# VCO_BFP420.net
KiCad netlist of a schematic drawn in Altium Designer
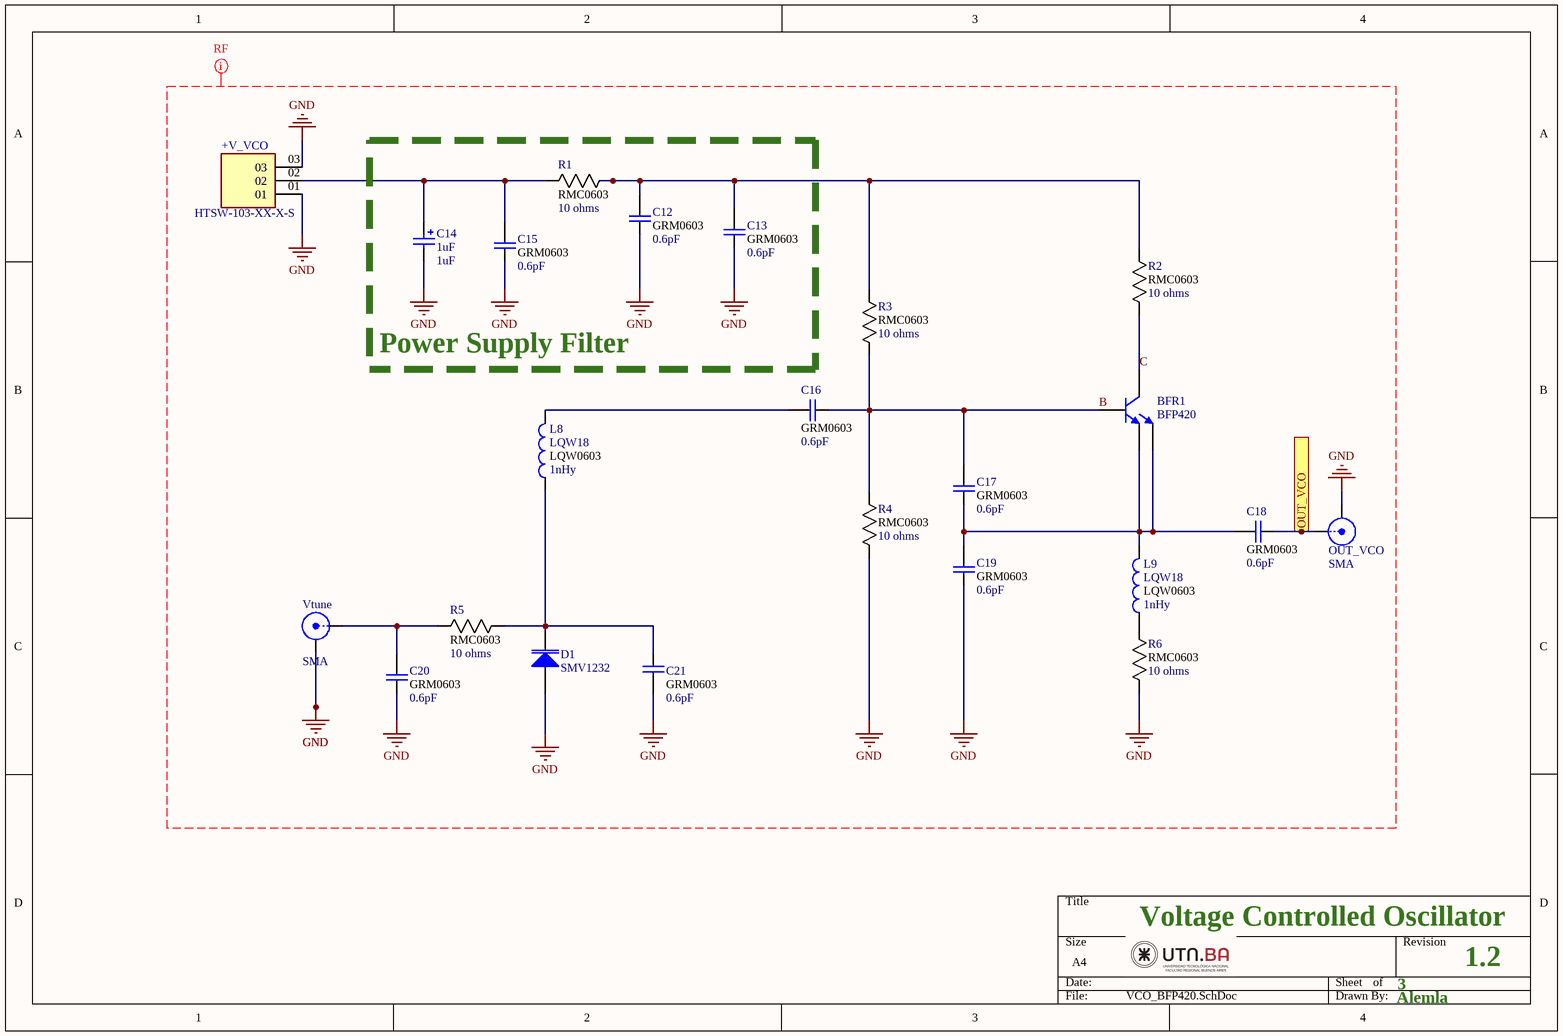
[diagram p0: VCO_BFP420.SchDoc]

(export (version "E")
  (design (tool "Eeschema 10.0.6"))
  (components
    (comp (ref "+V_VCO")
      (value "HTSW-103-XX-X-S")
      (footprint "SAMTEC_HTSW-103-XX-X-S")
      (description "Conn Unshrouded Header HDR 3 POS 2.54mm Solder ST Top Entry Thru-Hole Bag")
      (fields (field (name "MP") "HTSW-103-08-S-S") (field (name "MF") "Samtec"))
      (libsource (lib "HTSW-103-XX-X-S") (part "HTSW-103-XX-X-S"))
    )
    (comp (ref "BFR1")
      (value "BFP420")
      (footprint "SOT-343_N")
      (description "NPN Bipolar Transistor")
      (fields (field (name "PUBLISHER") "Altium Limited"))
      (libsource (lib "PCB_Project") (part "BFR460"))
    )
    (comp (ref "C12")
      (value "0.6pF")
      (footprint "GRM0603")
      (description "Capacitor GRM18 0603")
      (fields (field (name "Comment") "Cap 0603") (field (name "PUBLISHER") "Altium Limited"))
      (libsource (lib "Radar_RF_EAIII") (part "Cap"))
    )
    (comp (ref "C13")
      (value "0.6pF")
      (footprint "GRM0603")
      (description "Capacitor GRM18 0603")
      (fields (field (name "Comment") "Cap 0603") (field (name "PUBLISHER") "Altium Limited"))
      (libsource (lib "Radar_RF_EAIII") (part "Cap"))
    )
    (comp (ref "C14")
      (value "1uF")
      (footprint "6-0805_N")
      (description "Polarized Capacitor (Axial)")
      (fields (field (name "ALTIUM_VALUE") "1uF") (field (name "PUBLISHER") "Altium Limited"))
      (libsource (lib "PCB_Project") (part "Cap Pol2_1"))
    )
    (comp (ref "C15")
      (value "0.6pF")
      (footprint "GRM0603")
      (description "Capacitor GRM18 0603")
      (fields (field (name "Comment") "Cap 0603") (field (name "PUBLISHER") "Altium Limited"))
      (libsource (lib "Radar_RF_EAIII") (part "Cap"))
    )
    (comp (ref "C16")
      (value "0.6pF")
      (footprint "GRM0603")
      (description "Capacitor GRM18 0603")
      (fields (field (name "Comment") "Cap 0603") (field (name "PUBLISHER") "Altium Limited"))
      (libsource (lib "Radar_RF_EAIII") (part "Cap"))
    )
    (comp (ref "C17")
      (value "0.6pF")
      (footprint "GRM0603")
      (description "Capacitor GRM18 0603")
      (fields (field (name "Comment") "Cap 0603") (field (name "PUBLISHER") "Altium Limited"))
      (libsource (lib "Radar_RF_EAIII") (part "Cap"))
    )
    (comp (ref "C18")
      (value "0.6pF")
      (footprint "GRM0603")
      (description "Capacitor GRM18 0603")
      (fields (field (name "Comment") "Cap 0603") (field (name "PUBLISHER") "Altium Limited"))
      (libsource (lib "Radar_RF_EAIII") (part "Cap"))
    )
    (comp (ref "C19")
      (value "0.6pF")
      (footprint "GRM0603")
      (description "Capacitor GRM18 0603")
      (fields (field (name "Comment") "Cap 0603") (field (name "PUBLISHER") "Altium Limited"))
      (libsource (lib "Radar_RF_EAIII") (part "Cap"))
    )
    (comp (ref "C20")
      (value "0.6pF")
      (footprint "GRM0603")
      (description "Capacitor GRM18 0603")
      (fields (field (name "Comment") "Cap 0603") (field (name "PUBLISHER") "Altium Limited"))
      (libsource (lib "Radar_RF_EAIII") (part "Cap"))
    )
    (comp (ref "C21")
      (value "0.6pF")
      (footprint "GRM0603")
      (description "Capacitor GRM18 0603")
      (fields (field (name "Comment") "Cap 0603") (field (name "PUBLISHER") "Altium Limited"))
      (libsource (lib "Radar_RF_EAIII") (part "Cap"))
    )
    (comp (ref "D1")
      (value "SMV1232")
      (footprint "6-0805_N")
      (description "Variable Capacitance Diode")
      (fields (field (name "PUBLISHER") "Altium Limited"))
      (libsource (lib "Radar_RF_EAIII") (part "D Varactor"))
    )
    (comp (ref "L8")
      (value "LQW18")
      (footprint "INDC1608X100N")
      (description "Ind RF Chip Wirewound 18nH 5% 100MHz 40Q-Factor 550mA 0603 Paper T/R")
      (fields
        (field (name "MP") "LQW18AN18NJ00D")
        (field (name "PARAMETER 1") "LQW0603")
        (field (name "ALTIUM_VALUE") "1nHy")
      )
      (libsource (lib "Radar_RF_EAIII") (part "LQW18"))
    )
    (comp (ref "L9")
      (value "LQW18")
      (footprint "INDC1608X100N")
      (description "Ind RF Chip Wirewound 18nH 5% 100MHz 40Q-Factor 550mA 0603 Paper T/R")
      (fields
        (field (name "MP") "LQW18AN18NJ00D")
        (field (name "PARAMETER 1") "LQW0603")
        (field (name "ALTIUM_VALUE") "1nHy")
      )
      (libsource (lib "Radar_RF_EAIII") (part "LQW18"))
    )
    (comp (ref "OUT_VCO")
      (value "SMA")
      (footprint "SMA-142-0701-851")
      (description "SMA Straight Connector")
      (fields (field (name "PUBLISHER") "Altium Limited"))
      (libsource (lib "Radar_RF_EAIII") (part "SMA"))
    )
    (comp (ref "R1")
      (value "10 ohms")
      (footprint "RMC0603")
      (description "Resistor RMC0603")
      (fields (field (name "Comment") "Resistor"))
      (libsource (lib "Radar_RF_EAIII") (part "Resistor"))
    )
    (comp (ref "R2")
      (value "10 ohms")
      (footprint "RMC0603")
      (description "Resistor RMC0603")
      (fields (field (name "Comment") "Resistor"))
      (libsource (lib "Radar_RF_EAIII") (part "Resistor"))
    )
    (comp (ref "R3")
      (value "10 ohms")
      (footprint "RMC0603")
      (description "Resistor RMC0603")
      (fields (field (name "Comment") "Resistor"))
      (libsource (lib "Radar_RF_EAIII") (part "Resistor"))
    )
    (comp (ref "R4")
      (value "10 ohms")
      (footprint "RMC0603")
      (description "Resistor RMC0603")
      (fields (field (name "Comment") "Resistor"))
      (libsource (lib "Radar_RF_EAIII") (part "Resistor"))
    )
    (comp (ref "R5")
      (value "10 ohms")
      (footprint "RMC0603")
      (description "Resistor RMC0603")
      (fields (field (name "Comment") "Resistor"))
      (libsource (lib "Radar_RF_EAIII") (part "Resistor"))
    )
    (comp (ref "R6")
      (value "10 ohms")
      (footprint "RMC0603")
      (description "Resistor RMC0603")
      (fields (field (name "Comment") "Resistor"))
      (libsource (lib "Radar_RF_EAIII") (part "Resistor"))
    )
    (comp (ref "Vtune")
      (value "SMA")
      (footprint "SMA-142-0701-851")
      (description "SMA Straight Connector")
      (fields (field (name "PUBLISHER") "Altium Limited"))
      (libsource (lib "Radar_RF_EAIII") (part "SMA"))
    )
  )
  (nets
    (net (code "1") (name "/B") (class "Default")
      (node (ref "BFR1") (pin "4") (pinfunction "B_4") (pintype "passive"))
      (node (ref "C16") (pin "1") (pinfunction "1_1") (pintype "passive"))
      (node (ref "C17") (pin "2") (pinfunction "2_2") (pintype "passive"))
      (node (ref "R3") (pin "1") (pinfunction "1_1") (pintype "passive"))
      (node (ref "R4") (pin "2") (pinfunction "2_2") (pintype "passive"))
    )
    (net (code "2") (name "/C") (class "Default")
      (node (ref "BFR1") (pin "2") (pinfunction "C_2") (pintype "passive"))
      (node (ref "R2") (pin "1") (pinfunction "1_1") (pintype "passive"))
    )
    (net (code "3") (name "/OUT_VCO") (class "Default")
      (node (ref "C18") (pin "1") (pinfunction "1_1") (pintype "passive"))
      (node (ref "OUT_VCO") (pin "1") (pinfunction "X_1") (pintype "passive"))
    )
    (net (code "4") (name "GND") (class "Default")
      (node (ref "+V_VCO") (pin "01") (pinfunction "01_01") (pintype "passive"))
      (node (ref "+V_VCO") (pin "03") (pinfunction "03_03") (pintype "passive"))
      (node (ref "C12") (pin "1") (pinfunction "1_1") (pintype "passive"))
      (node (ref "C13") (pin "1") (pinfunction "1_1") (pintype "passive"))
      (node (ref "C14") (pin "2") (pinfunction "2_2") (pintype "passive"))
      (node (ref "C15") (pin "1") (pinfunction "1_1") (pintype "passive"))
      (node (ref "C19") (pin "1") (pinfunction "1_1") (pintype "passive"))
      (node (ref "C20") (pin "1") (pinfunction "1_1") (pintype "passive"))
      (node (ref "C21") (pin "2") (pinfunction "2_2") (pintype "passive"))
      (node (ref "D1") (pin "1") (pinfunction "A_1") (pintype "passive"))
      (node (ref "OUT_VCO") (pin "2") (pinfunction "Y_2") (pintype "passive"))
      (node (ref "R4") (pin "1") (pinfunction "1_1") (pintype "passive"))
      (node (ref "R6") (pin "1") (pinfunction "1_1") (pintype "passive"))
      (node (ref "Vtune") (pin "2") (pinfunction "Y_2") (pintype "passive"))
    )
    (net (code "5") (name "Net-(+V_VCO-Pad02)") (class "Default")
      (node (ref "+V_VCO") (pin "02") (pinfunction "02_02") (pintype "passive"))
      (node (ref "C14") (pin "1") (pinfunction "1_1") (pintype "passive"))
      (node (ref "C15") (pin "2") (pinfunction "2_2") (pintype "passive"))
      (node (ref "R1") (pin "1") (pinfunction "1_1") (pintype "passive"))
    )
    (net (code "6") (name "Net-(BFR1-E-Pad1)") (class "Default")
      (node (ref "BFR1") (pin "1") (pinfunction "E_1") (pintype "passive"))
      (node (ref "BFR1") (pin "3") (pinfunction "E_3") (pintype "passive"))
      (node (ref "C17") (pin "1") (pinfunction "1_1") (pintype "passive"))
      (node (ref "C18") (pin "2") (pinfunction "2_2") (pintype "passive"))
      (node (ref "C19") (pin "2") (pinfunction "2_2") (pintype "passive"))
      (node (ref "L9") (pin "2") (pinfunction "2_2") (pintype "passive"))
    )
    (net (code "7") (name "Net-(C12-Pad2)") (class "Default")
      (node (ref "C12") (pin "2") (pinfunction "2_2") (pintype "passive"))
      (node (ref "C13") (pin "2") (pinfunction "2_2") (pintype "passive"))
      (node (ref "R1") (pin "2") (pinfunction "2_2") (pintype "passive"))
      (node (ref "R2") (pin "2") (pinfunction "2_2") (pintype "passive"))
      (node (ref "R3") (pin "2") (pinfunction "2_2") (pintype "passive"))
    )
    (net (code "8") (name "Net-(C16-Pad2)") (class "Default")
      (node (ref "C16") (pin "2") (pinfunction "2_2") (pintype "passive"))
      (node (ref "L8") (pin "2") (pinfunction "2_2") (pintype "passive"))
    )
    (net (code "9") (name "Net-(D1-K)") (class "Default")
      (node (ref "C21") (pin "1") (pinfunction "1_1") (pintype "passive"))
      (node (ref "D1") (pin "2") (pinfunction "K_2") (pintype "passive"))
      (node (ref "L8") (pin "1") (pinfunction "1_1") (pintype "passive"))
      (node (ref "R5") (pin "1") (pinfunction "1_1") (pintype "passive"))
    )
    (net (code "10") (name "Net-(L9-Pad1)") (class "Default")
      (node (ref "L9") (pin "1") (pinfunction "1_1") (pintype "passive"))
      (node (ref "R6") (pin "2") (pinfunction "2_2") (pintype "passive"))
    )
    (net (code "11") (name "Net-(Vtune-X)") (class "Default")
      (node (ref "C20") (pin "2") (pinfunction "2_2") (pintype "passive"))
      (node (ref "R5") (pin "2") (pinfunction "2_2") (pintype "passive"))
      (node (ref "Vtune") (pin "1") (pinfunction "X_1") (pintype "passive"))
    )
  )
)
